# 5_AnalogSense.net
KiCad netlist of a schematic drawn in Altium Designer
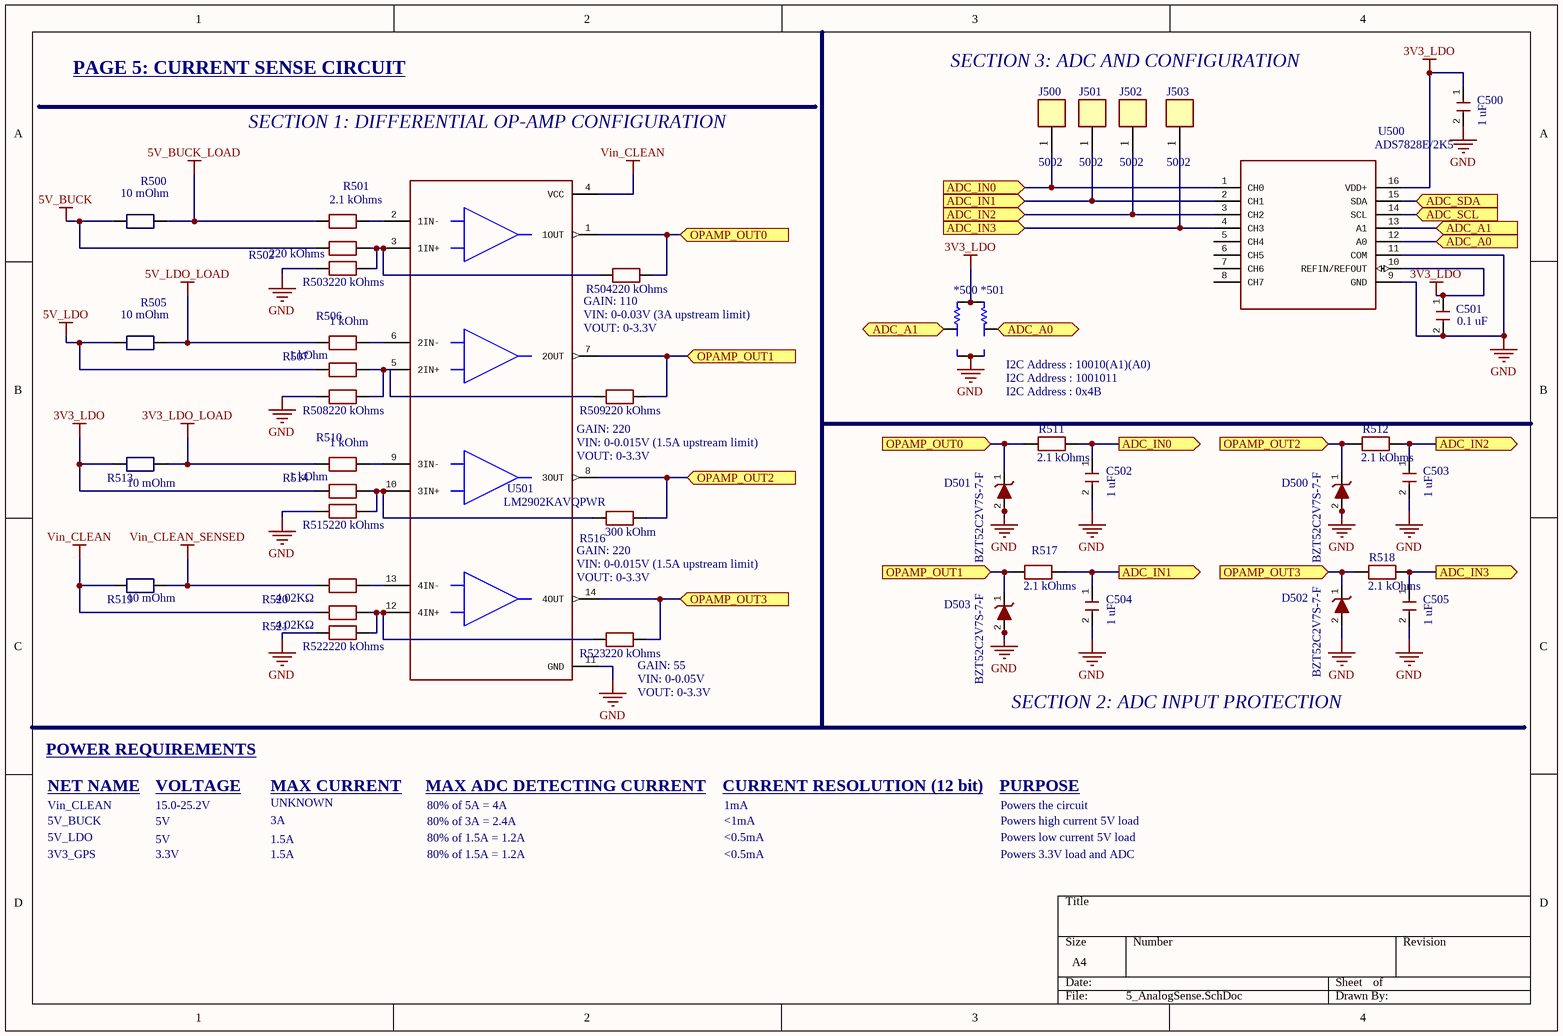
[diagram p0: 5_AnalogSense.SchDoc]

(export (version "E")
  (design (tool "Eeschema 10.0.6"))
  (components
    (comp (ref "*500")
      (value "3-pin selection 0603")
      (footprint "3-PIN SELECTION CIRCUIT")
      (libsource (lib "Miscellaneous") (part "3-pin selection 0603"))
    )
    (comp (ref "*501")
      (value "3-pin selection 0603")
      (footprint "3-PIN SELECTION CIRCUIT")
      (libsource (lib "Miscellaneous") (part "3-pin selection 0603"))
    )
    (comp (ref "C500")
      (value "1 uF")
      (footprint "CAP_0603")
      (description "Cap Ceramic 1uF 50V 0603")
      (fields
        (field (name "MANUFACTURER") "Murata Electronics")
        (field (name "PARTNUMBER") "GCM188R71C105KA64")
      )
      (libsource (lib "Passives") (part "GRT188R61H105KE13D"))
    )
    (comp (ref "C501")
      (value "0.1 uF")
      (footprint "CAP_0603")
      (description "Cap Ceramic 0.1uF 50V 0603")
      (fields (field (name "PARTNUMBER") "CL10B104KB8NNNC"))
      (libsource (lib "Passives") (part "CL10B104KB8NNNC"))
    )
    (comp (ref "C502")
      (value "1 uF")
      (footprint "CAP_0603")
      (description "Cap Ceramic 1uF 50V 0603")
      (fields
        (field (name "MANUFACTURER") "Murata Electronics")
        (field (name "PARTNUMBER") "GCM188R71C105KA64")
      )
      (libsource (lib "Passives") (part "GRT188R61H105KE13D"))
    )
    (comp (ref "C503")
      (value "1 uF")
      (footprint "CAP_0603")
      (description "Cap Ceramic 1uF 50V 0603")
      (fields
        (field (name "MANUFACTURER") "Murata Electronics")
        (field (name "PARTNUMBER") "GCM188R71C105KA64")
      )
      (libsource (lib "Passives") (part "GRT188R61H105KE13D"))
    )
    (comp (ref "C504")
      (value "1 uF")
      (footprint "CAP_0603")
      (description "Cap Ceramic 1uF 50V 0603")
      (fields
        (field (name "MANUFACTURER") "Murata Electronics")
        (field (name "PARTNUMBER") "GCM188R71C105KA64")
      )
      (libsource (lib "Passives") (part "GRT188R61H105KE13D"))
    )
    (comp (ref "C505")
      (value "1 uF")
      (footprint "CAP_0603")
      (description "Cap Ceramic 1uF 50V 0603")
      (fields
        (field (name "MANUFACTURER") "Murata Electronics")
        (field (name "PARTNUMBER") "GCM188R71C105KA64")
      )
      (libsource (lib "Passives") (part "GRT188R61H105KE13D"))
    )
    (comp (ref "D500")
      (value "BZT52C2V7S-7-F")
      (footprint "DIODE_DO-214AC")
      (description "Diode Zener 2V7")
      (fields (field (name "MANUFACTURER") "Diodes Inc"))
      (libsource (lib "Passives") (part "BZT52C2V7S-7-F"))
    )
    (comp (ref "D501")
      (value "BZT52C2V7S-7-F")
      (footprint "DIODE_DO-214AC")
      (description "Diode Zener 2V7")
      (fields (field (name "MANUFACTURER") "Diodes Inc"))
      (libsource (lib "Passives") (part "BZT52C2V7S-7-F"))
    )
    (comp (ref "D502")
      (value "BZT52C2V7S-7-F")
      (footprint "DIODE_DO-214AC")
      (description "Diode Zener 2V7")
      (fields (field (name "MANUFACTURER") "Diodes Inc"))
      (libsource (lib "Passives") (part "BZT52C2V7S-7-F"))
    )
    (comp (ref "D503")
      (value "BZT52C2V7S-7-F")
      (footprint "DIODE_DO-214AC")
      (description "Diode Zener 2V7")
      (fields (field (name "MANUFACTURER") "Diodes Inc"))
      (libsource (lib "Passives") (part "BZT52C2V7S-7-F"))
    )
    (comp (ref "J500")
      (value "5002")
      (footprint "Miscellaneous:KEYSTONE_5002")
      (description "Test Point Ring Keystone")
      (fields (field (name "MANUFACTURER") "Keystone Electronics"))
      (libsource (lib "Miscellaneous") (part "5002"))
    )
    (comp (ref "J501")
      (value "5002")
      (footprint "Miscellaneous:KEYSTONE_5002")
      (description "Test Point Ring Keystone")
      (fields (field (name "MANUFACTURER") "Keystone Electronics"))
      (libsource (lib "Miscellaneous") (part "5002"))
    )
    (comp (ref "J502")
      (value "5002")
      (footprint "Miscellaneous:KEYSTONE_5002")
      (description "Test Point Ring Keystone")
      (fields (field (name "MANUFACTURER") "Keystone Electronics"))
      (libsource (lib "Miscellaneous") (part "5002"))
    )
    (comp (ref "J503")
      (value "5002")
      (footprint "Miscellaneous:KEYSTONE_5002")
      (description "Test Point Ring Keystone")
      (fields (field (name "MANUFACTURER") "Keystone Electronics"))
      (libsource (lib "Miscellaneous") (part "5002"))
    )
    (comp (ref "R500")
      (value "10 mOhm")
      (footprint "RES_0805")
      (description "Res 10mOhm 1/2W Sense Resistor 0805")
      (fields (field (name "PARTNUMBER") "ERJ6CWFR010V"))
      (libsource (lib "Passives") (part "ERJ6CWFR010V"))
    )
    (comp (ref "R501")
      (value "2.1 kOhms")
      (footprint "RES_0603")
      (description "Res 2.1KOhms 1/10W 0603")
      (fields (field (name "PARTNUMBER") "ERJ-3EKF2101V"))
      (libsource (lib "Passives") (part "ERJ-3EKF2101VRC0603N_PAN-M"))
    )
    (comp (ref "R502")
      (value "220 kOhms")
      (footprint "RES_0603")
      (description "Res 220kOhms 1/10W 0603")
      (fields (field (name "PARTNUMBER") "ERJ3EKF2203V"))
      (libsource (lib "Passives") (part "ERJ3EKF2203V"))
    )
    (comp (ref "R503")
      (value "220 kOhms")
      (footprint "RES_0603")
      (description "Res 220kOhms 1/10W 0603")
      (fields (field (name "PARTNUMBER") "ERJ3EKF2203V"))
      (libsource (lib "Passives") (part "ERJ3EKF2203V"))
    )
    (comp (ref "R504")
      (value "220 kOhms")
      (footprint "RES_0603")
      (description "Res 220kOhms 1/10W 0603")
      (fields (field (name "PARTNUMBER") "ERJ3EKF2203V"))
      (libsource (lib "Passives") (part "ERJ3EKF2203V"))
    )
    (comp (ref "R505")
      (value "10 mOhm")
      (footprint "RES_0805")
      (description "Res 10mOhm 1/2W Sense Resistor 0805")
      (fields (field (name "PARTNUMBER") "ERJ6CWFR010V"))
      (libsource (lib "Passives") (part "ERJ6CWFR010V"))
    )
    (comp (ref "R506")
      (value "1 kOhm")
      (footprint "RES_0603")
      (description "Res 1kOhm 1/10W 0603")
      (fields (field (name "PARTNUMBER") "ERJ3GEYJ102V"))
      (libsource (lib "Passives") (part "ERJ3GEYJ102V"))
    )
    (comp (ref "R507")
      (value "1 kOhm")
      (footprint "RES_0603")
      (description "Res 1kOhm 1/10W 0603")
      (fields (field (name "PARTNUMBER") "ERJ3GEYJ102V"))
      (libsource (lib "Passives") (part "ERJ3GEYJ102V"))
    )
    (comp (ref "R508")
      (value "220 kOhms")
      (footprint "RES_0603")
      (description "Res 220kOhms 1/10W 0603")
      (fields (field (name "PARTNUMBER") "ERJ3EKF2203V"))
      (libsource (lib "Passives") (part "ERJ3EKF2203V"))
    )
    (comp (ref "R509")
      (value "220 kOhms")
      (footprint "RES_0603")
      (description "Res 220kOhms 1/10W 0603")
      (fields (field (name "PARTNUMBER") "ERJ3EKF2203V"))
      (libsource (lib "Passives") (part "ERJ3EKF2203V"))
    )
    (comp (ref "R510")
      (value "1 kOhm")
      (footprint "RES_0603")
      (description "Res 1kOhm 1/10W 0603")
      (fields (field (name "PARTNUMBER") "ERJ3GEYJ102V"))
      (libsource (lib "Passives") (part "ERJ3GEYJ102V"))
    )
    (comp (ref "R511")
      (value "2.1 kOhms")
      (footprint "RES_0603")
      (description "Res 2.1KOhms 1/10W 0603")
      (fields (field (name "PARTNUMBER") "ERJ-3EKF2101V"))
      (libsource (lib "Passives") (part "ERJ-3EKF2101V"))
    )
    (comp (ref "R512")
      (value "2.1 kOhms")
      (footprint "RES_0603")
      (description "Res 2.1KOhms 1/10W 0603")
      (fields (field (name "PARTNUMBER") "ERJ-3EKF2101V"))
      (libsource (lib "Passives") (part "ERJ-3EKF2101V"))
    )
    (comp (ref "R513")
      (value "10 mOhm")
      (footprint "RES_0805")
      (description "Res 10mOhm 1/2W Sense Resistor 0805")
      (fields (field (name "PARTNUMBER") "ERJ6CWFR010V"))
      (libsource (lib "Passives") (part "ERJ6CWFR010V"))
    )
    (comp (ref "R514")
      (value "1 kOhm")
      (footprint "RES_0603")
      (description "Res 1kOhm 1/10W 0603")
      (fields (field (name "PARTNUMBER") "ERJ3GEYJ102V"))
      (libsource (lib "Passives") (part "ERJ3GEYJ102V"))
    )
    (comp (ref "R515")
      (value "220 kOhms")
      (footprint "RES_0603")
      (description "Res 220kOhms 1/10W 0603")
      (fields (field (name "PARTNUMBER") "ERJ3EKF2203V"))
      (libsource (lib "Passives") (part "ERJ3EKF2203V"))
    )
    (comp (ref "R516")
      (value "300 kOhm")
      (footprint "RES_0603")
      (description "Res 300kOhm 1/10W 0603")
      (fields (field (name "PARTNUMBER") "ERJ3GEYJ304V"))
      (libsource (lib "Passives") (part "ERJ3GEYJ304V"))
    )
    (comp (ref "R517")
      (value "2.1 kOhms")
      (footprint "RES_0603")
      (description "Res 2.1KOhms 1/10W 0603")
      (fields (field (name "PARTNUMBER") "ERJ-3EKF2101V"))
      (libsource (lib "Passives") (part "ERJ-3EKF2101V"))
    )
    (comp (ref "R518")
      (value "2.1 kOhms")
      (footprint "RES_0603")
      (description "Res 2.1KOhms 1/10W 0603")
      (fields (field (name "PARTNUMBER") "ERJ-3EKF2101V"))
      (libsource (lib "Passives") (part "ERJ-3EKF2101V"))
    )
    (comp (ref "R519")
      (value "10 mOhm")
      (footprint "RES_0805")
      (description "Res 10mOhm 1/2W Sense Resistor 0805")
      (fields (field (name "PARTNUMBER") "ERJ6CWFR010V"))
      (libsource (lib "Passives") (part "ERJ6CWFR010V"))
    )
    (comp (ref "R520")
      (value "4.02KΩ")
      (footprint "RES_0603")
      (description "Res 4.02KOhm 1/10W 0603")
      (fields (field (name "PARTNUMBER") "ERJ3GEYJ200V") (field (name "Comment") "ERA3AEB4021V"))
      (libsource (lib "Passives") (part "ERA3AEB4021V"))
    )
    (comp (ref "R521")
      (value "4.02KΩ")
      (footprint "RES_0603")
      (description "Res 4.02KOhm 1/10W 0603")
      (fields (field (name "PARTNUMBER") "ERJ3GEYJ200V") (field (name "Comment") "ERA3AEB4021V"))
      (libsource (lib "Passives") (part "ERA3AEB4021V"))
    )
    (comp (ref "R522")
      (value "220 kOhms")
      (footprint "RES_0603")
      (description "Res 220kOhms 1/10W 0603")
      (fields (field (name "PARTNUMBER") "ERJ3EKF2203V"))
      (libsource (lib "Passives") (part "ERJ3EKF2203V"))
    )
    (comp (ref "R523")
      (value "220 kOhms")
      (footprint "RES_0603")
      (description "Res 220kOhms 1/10W 0603")
      (fields (field (name "PARTNUMBER") "ERJ3EKF2203V"))
      (libsource (lib "Passives") (part "ERJ3EKF2203V"))
    )
    (comp (ref "U500")
      (value "ADS7828E/2K5")
      (footprint "ADC-TSSOP-16")
      (description "ADC 12bit 8Ch")
      (fields (field (name "MANUFACTURER") "Texas Instruments"))
      (libsource (lib "Sensors") (part "ADS7828E/2K5"))
    )
    (comp (ref "U501")
      (value "LM2902KAVQPWR")
      (footprint "OPAMP_TSSOP-14")
      (description "OpAmps 4Channel")
      (fields (field (name "MANUFACTURER") "Texas Instruments"))
      (libsource (lib "FETs") (part "LM2902KAVQPWR"))
    )
  )
  (nets
    (net (code "1") (name "/ADC_A0") (class "Default")
      (node (ref "*501") (pin "2") (pinfunction "2_2") (pintype "passive"))
      (node (ref "U500") (pin "12") (pinfunction "A0_12") (pintype "passive"))
    )
    (net (code "2") (name "/ADC_A1") (class "Default")
      (node (ref "*500") (pin "2") (pinfunction "2_2") (pintype "passive"))
      (node (ref "U500") (pin "13") (pinfunction "A1_13") (pintype "passive"))
    )
    (net (code "3") (name "/ADC_IN0") (class "Default")
      (node (ref "C502") (pin "1") (pinfunction "1_1") (pintype "passive"))
      (node (ref "J500") (pin "1") (pintype "passive"))
      (node (ref "R511") (pin "2") (pinfunction "2_2") (pintype "passive"))
      (node (ref "U500") (pin "1") (pinfunction "CH0_1") (pintype "passive"))
    )
    (net (code "4") (name "/ADC_IN1") (class "Default")
      (node (ref "C504") (pin "1") (pinfunction "1_1") (pintype "passive"))
      (node (ref "J501") (pin "1") (pintype "passive"))
      (node (ref "R517") (pin "2") (pinfunction "2_2") (pintype "passive"))
      (node (ref "U500") (pin "2") (pinfunction "CH1_2") (pintype "passive"))
    )
    (net (code "5") (name "/ADC_IN2") (class "Default")
      (node (ref "C503") (pin "1") (pinfunction "1_1") (pintype "passive"))
      (node (ref "J502") (pin "1") (pintype "passive"))
      (node (ref "R512") (pin "2") (pinfunction "2_2") (pintype "passive"))
      (node (ref "U500") (pin "3") (pinfunction "CH2_3") (pintype "passive"))
    )
    (net (code "6") (name "/ADC_IN3") (class "Default")
      (node (ref "C505") (pin "1") (pinfunction "1_1") (pintype "passive"))
      (node (ref "J503") (pin "1") (pintype "passive"))
      (node (ref "R518") (pin "2") (pinfunction "2_2") (pintype "passive"))
      (node (ref "U500") (pin "4") (pinfunction "CH3_4") (pintype "passive"))
    )
    (net (code "7") (name "/ADC_SCL") (class "Default")
      (node (ref "U500") (pin "14") (pinfunction "SCL_14") (pintype "passive"))
    )
    (net (code "8") (name "/ADC_SDA") (class "Default")
      (node (ref "U500") (pin "15") (pinfunction "SDA_15") (pintype "passive"))
    )
    (net (code "9") (name "/OPAMP_OUT0") (class "Default")
      (node (ref "D501") (pin "1") (pinfunction "1_1") (pintype "passive"))
      (node (ref "R504") (pin "2") (pinfunction "2_2") (pintype "passive"))
      (node (ref "R511") (pin "1") (pinfunction "1_1") (pintype "passive"))
      (node (ref "U501") (pin "1") (pinfunction "1OUT_1") (pintype "output"))
    )
    (net (code "10") (name "/OPAMP_OUT1") (class "Default")
      (node (ref "D503") (pin "1") (pinfunction "1_1") (pintype "passive"))
      (node (ref "R509") (pin "2") (pinfunction "2_2") (pintype "passive"))
      (node (ref "R517") (pin "1") (pinfunction "1_1") (pintype "passive"))
      (node (ref "U501") (pin "7") (pinfunction "2OUT_7") (pintype "output"))
    )
    (net (code "11") (name "/OPAMP_OUT2") (class "Default")
      (node (ref "D500") (pin "1") (pinfunction "1_1") (pintype "passive"))
      (node (ref "R512") (pin "1") (pinfunction "1_1") (pintype "passive"))
      (node (ref "R516") (pin "2") (pinfunction "2_2") (pintype "passive"))
      (node (ref "U501") (pin "8") (pinfunction "3OUT_8") (pintype "output"))
    )
    (net (code "12") (name "/OPAMP_OUT3") (class "Default")
      (node (ref "D502") (pin "1") (pinfunction "1_1") (pintype "passive"))
      (node (ref "R518") (pin "1") (pinfunction "1_1") (pintype "passive"))
      (node (ref "R523") (pin "2") (pinfunction "2_2") (pintype "passive"))
      (node (ref "U501") (pin "14") (pinfunction "4OUT_14") (pintype "output"))
    )
    (net (code "13") (name "3V3_LDO") (class "Default")
      (node (ref "*500") (pin "3") (pinfunction "3_3") (pintype "passive"))
      (node (ref "*501") (pin "3") (pinfunction "3_3") (pintype "passive"))
      (node (ref "C500") (pin "1") (pinfunction "1_1") (pintype "passive"))
      (node (ref "C501") (pin "1") (pinfunction "1_1") (pintype "passive"))
      (node (ref "R513") (pin "1") (pinfunction "1_1") (pintype "passive"))
      (node (ref "R514") (pin "1") (pinfunction "1_1") (pintype "passive"))
      (node (ref "U500") (pin "10") (pinfunction "REFIN/REFOUT_10") (pintype "bidirectional"))
      (node (ref "U500") (pin "16") (pinfunction "VDD+_16") (pintype "power_in"))
    )
    (net (code "14") (name "3V3_LDO_LOAD") (class "Default")
      (node (ref "R510") (pin "1") (pinfunction "1_1") (pintype "passive"))
      (node (ref "R513") (pin "2") (pinfunction "2_2") (pintype "passive"))
    )
    (net (code "15") (name "5V_BUCK") (class "Default")
      (node (ref "R500") (pin "1") (pinfunction "1_1") (pintype "passive"))
      (node (ref "R502") (pin "1") (pinfunction "1_1") (pintype "passive"))
    )
    (net (code "16") (name "5V_BUCK_LOAD") (class "Default")
      (node (ref "R500") (pin "2") (pinfunction "2_2") (pintype "passive"))
      (node (ref "R501") (pin "1") (pinfunction "1_1") (pintype "passive"))
    )
    (net (code "17") (name "5V_LDO") (class "Default")
      (node (ref "R505") (pin "1") (pinfunction "1_1") (pintype "passive"))
      (node (ref "R507") (pin "1") (pinfunction "1_1") (pintype "passive"))
    )
    (net (code "18") (name "5V_LDO_LOAD") (class "Default")
      (node (ref "R505") (pin "2") (pinfunction "2_2") (pintype "passive"))
      (node (ref "R506") (pin "1") (pinfunction "1_1") (pintype "passive"))
    )
    (net (code "19") (name "GND") (class "Default")
      (node (ref "*500") (pin "1") (pinfunction "1_1") (pintype "passive"))
      (node (ref "*501") (pin "1") (pinfunction "1_1") (pintype "passive"))
      (node (ref "C500") (pin "2") (pinfunction "2_2") (pintype "passive"))
      (node (ref "C501") (pin "2") (pinfunction "2_2") (pintype "passive"))
      (node (ref "C502") (pin "2") (pinfunction "2_2") (pintype "passive"))
      (node (ref "C503") (pin "2") (pinfunction "2_2") (pintype "passive"))
      (node (ref "C504") (pin "2") (pinfunction "2_2") (pintype "passive"))
      (node (ref "C505") (pin "2") (pinfunction "2_2") (pintype "passive"))
      (node (ref "D500") (pin "2") (pinfunction "2_2") (pintype "passive"))
      (node (ref "D501") (pin "2") (pinfunction "2_2") (pintype "passive"))
      (node (ref "D502") (pin "2") (pinfunction "2_2") (pintype "passive"))
      (node (ref "D503") (pin "2") (pinfunction "2_2") (pintype "passive"))
      (node (ref "R503") (pin "1") (pinfunction "1_1") (pintype "passive"))
      (node (ref "R508") (pin "1") (pinfunction "1_1") (pintype "passive"))
      (node (ref "R515") (pin "1") (pinfunction "1_1") (pintype "passive"))
      (node (ref "R522") (pin "1") (pinfunction "1_1") (pintype "passive"))
      (node (ref "U500") (pin "11") (pinfunction "COM_11") (pintype "passive"))
      (node (ref "U500") (pin "9") (pinfunction "GND_9") (pintype "power_in"))
      (node (ref "U501") (pin "11") (pinfunction "GND_11") (pintype "power_in"))
    )
    (net (code "20") (name "Net-(U501-1IN+)") (class "Default")
      (node (ref "R502") (pin "2") (pinfunction "2_2") (pintype "passive"))
      (node (ref "R503") (pin "2") (pinfunction "2_2") (pintype "passive"))
      (node (ref "R504") (pin "1") (pinfunction "1_1") (pintype "passive"))
      (node (ref "U501") (pin "3") (pinfunction "1IN+_3") (pintype "passive"))
    )
    (net (code "21") (name "Net-(U501-1IN-)") (class "Default")
      (node (ref "R501") (pin "2") (pinfunction "2_2") (pintype "passive"))
      (node (ref "U501") (pin "2") (pinfunction "1IN-_2") (pintype "passive"))
    )
    (net (code "22") (name "Net-(U501-2IN+)") (class "Default")
      (node (ref "R507") (pin "2") (pinfunction "2_2") (pintype "passive"))
      (node (ref "R508") (pin "2") (pinfunction "2_2") (pintype "passive"))
      (node (ref "R509") (pin "1") (pinfunction "1_1") (pintype "passive"))
      (node (ref "U501") (pin "5") (pinfunction "2IN+_5") (pintype "passive"))
    )
    (net (code "23") (name "Net-(U501-2IN-)") (class "Default")
      (node (ref "R506") (pin "2") (pinfunction "2_2") (pintype "passive"))
      (node (ref "U501") (pin "6") (pinfunction "2IN-_6") (pintype "passive"))
    )
    (net (code "24") (name "Net-(U501-3IN+)") (class "Default")
      (node (ref "R514") (pin "2") (pinfunction "2_2") (pintype "passive"))
      (node (ref "R515") (pin "2") (pinfunction "2_2") (pintype "passive"))
      (node (ref "R516") (pin "1") (pinfunction "1_1") (pintype "passive"))
      (node (ref "U501") (pin "10") (pinfunction "3IN+_10") (pintype "passive"))
    )
    (net (code "25") (name "Net-(U501-3IN-)") (class "Default")
      (node (ref "R510") (pin "2") (pinfunction "2_2") (pintype "passive"))
      (node (ref "U501") (pin "9") (pinfunction "3IN-_9") (pintype "passive"))
    )
    (net (code "26") (name "Net-(U501-4IN+)") (class "Default")
      (node (ref "R521") (pin "2") (pinfunction "2_2") (pintype "passive"))
      (node (ref "R522") (pin "2") (pinfunction "2_2") (pintype "passive"))
      (node (ref "R523") (pin "1") (pinfunction "1_1") (pintype "passive"))
      (node (ref "U501") (pin "12") (pinfunction "4IN+_12") (pintype "passive"))
    )
    (net (code "27") (name "Net-(U501-4IN-)") (class "Default")
      (node (ref "R520") (pin "2") (pinfunction "2_2") (pintype "passive"))
      (node (ref "U501") (pin "13") (pinfunction "4IN-_13") (pintype "passive"))
    )
    (net (code "28") (name "Vin_CLEAN") (class "Default")
      (node (ref "R519") (pin "1") (pinfunction "1_1") (pintype "passive"))
      (node (ref "R521") (pin "1") (pinfunction "1_1") (pintype "passive"))
      (node (ref "U501") (pin "4") (pinfunction "VCC_4") (pintype "power_in"))
    )
    (net (code "29") (name "Vin_CLEAN_SENSED") (class "Default")
      (node (ref "R519") (pin "2") (pinfunction "2_2") (pintype "passive"))
      (node (ref "R520") (pin "1") (pinfunction "1_1") (pintype "passive"))
    )
    (net (code "30") (name "unconnected-(U500-CH4-Pad5)") (class "Default")
      (node (ref "U500") (pin "5") (pinfunction "CH4_5") (pintype "passive"))
    )
    (net (code "31") (name "unconnected-(U500-CH5-Pad6)") (class "Default")
      (node (ref "U500") (pin "6") (pinfunction "CH5_6") (pintype "passive"))
    )
    (net (code "32") (name "unconnected-(U500-CH6-Pad7)") (class "Default")
      (node (ref "U500") (pin "7") (pinfunction "CH6_7") (pintype "passive"))
    )
    (net (code "33") (name "unconnected-(U500-CH7-Pad8)") (class "Default")
      (node (ref "U500") (pin "8") (pinfunction "CH7_8") (pintype "passive"))
    )
  )
)
